# ADUM1250ARZ_v_02.net
KiCad netlist of a schematic drawn in EAGLE
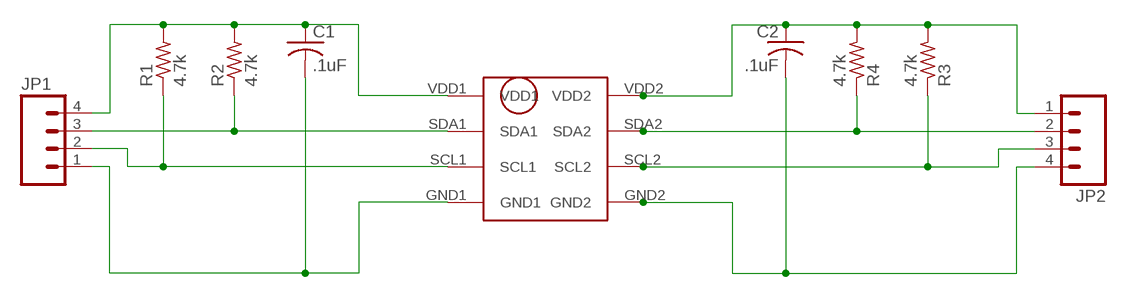
[diagram p0: schematic, sheet 1]

(export (version "E")
  (design (tool "Eeschema 10.0.6"))
  (components
    (comp (ref "C1")
      (value ".1uF")
      (footprint "eagle-import:C0402")
      (libsource (lib "eagle-import") (part "C-USC0402"))
    )
    (comp (ref "C2")
      (value ".1uF")
      (footprint "eagle-import:C0402")
      (libsource (lib "eagle-import") (part "C-USC0402"))
    )
    (comp (ref "JP1")
      (value "M04PTH")
      (footprint "eagle-import:1X04")
      (libsource (lib "eagle-import") (part "M04PTH"))
    )
    (comp (ref "JP2")
      (value "M04PTH")
      (footprint "eagle-import:1X04")
      (libsource (lib "eagle-import") (part "M04PTH"))
    )
    (comp (ref "R1")
      (value "4.7k")
      (footprint "eagle-import:R0402")
      (libsource (lib "eagle-import") (part "R-US_R0402"))
    )
    (comp (ref "R2")
      (value "4.7k")
      (footprint "eagle-import:R0402")
      (libsource (lib "eagle-import") (part "R-US_R0402"))
    )
    (comp (ref "R3")
      (value "4.7k")
      (footprint "eagle-import:R0402")
      (libsource (lib "eagle-import") (part "R-US_R0402"))
    )
    (comp (ref "R4")
      (value "4.7k")
      (footprint "eagle-import:R0402")
      (libsource (lib "eagle-import") (part "R-US_R0402"))
    )
    (comp (ref "U$1")
      (value "ADUM1250ARZ")
      (footprint "eagle-import:ADUM1250ARZ")
      (libsource (lib "eagle-import") (part "ADUM1250ARZ"))
    )
  )
  (nets
    (net (code "1") (name "/GND") (class "Default")
      (node (ref "C1") (pin "2") (pinfunction "2_2") (pintype "passive"))
      (node (ref "C2") (pin "2") (pinfunction "2_2") (pintype "passive"))
      (node (ref "JP1") (pin "1") (pinfunction "1_1") (pintype "passive"))
      (node (ref "JP2") (pin "4") (pinfunction "4_4") (pintype "passive"))
      (node (ref "U$1") (pin "GND1") (pinfunction "GND1_GND1") (pintype "bidirectional"))
      (node (ref "U$1") (pin "GND2") (pinfunction "GND2_GND2") (pintype "bidirectional"))
    )
    (net (code "2") (name "Net-(C1-Pad1)") (class "Default")
      (node (ref "C1") (pin "1") (pinfunction "1_1") (pintype "passive"))
      (node (ref "JP1") (pin "4") (pinfunction "4_4") (pintype "passive"))
      (node (ref "R1") (pin "2") (pinfunction "2_2") (pintype "passive"))
      (node (ref "R2") (pin "2") (pinfunction "2_2") (pintype "passive"))
      (node (ref "U$1") (pin "VDD1") (pinfunction "VDD1_VDD1") (pintype "bidirectional"))
    )
    (net (code "3") (name "Net-(C2-Pad1)") (class "Default")
      (node (ref "C2") (pin "1") (pinfunction "1_1") (pintype "passive"))
      (node (ref "JP2") (pin "1") (pinfunction "1_1") (pintype "passive"))
      (node (ref "R3") (pin "2") (pinfunction "2_2") (pintype "passive"))
      (node (ref "R4") (pin "2") (pinfunction "2_2") (pintype "passive"))
      (node (ref "U$1") (pin "VDD2") (pinfunction "VDD2_VDD2") (pintype "bidirectional"))
    )
    (net (code "4") (name "Net-(JP1-Pad2)") (class "Default")
      (node (ref "JP1") (pin "2") (pinfunction "2_2") (pintype "passive"))
      (node (ref "R1") (pin "1") (pinfunction "1_1") (pintype "passive"))
      (node (ref "U$1") (pin "SCL1") (pinfunction "SCL1_SCL1") (pintype "bidirectional"))
    )
    (net (code "5") (name "Net-(JP1-Pad3)") (class "Default")
      (node (ref "JP1") (pin "3") (pinfunction "3_3") (pintype "passive"))
      (node (ref "R2") (pin "1") (pinfunction "1_1") (pintype "passive"))
      (node (ref "U$1") (pin "SDA1") (pinfunction "SDA1_SDA1") (pintype "bidirectional"))
    )
    (net (code "6") (name "Net-(JP2-Pad2)") (class "Default")
      (node (ref "JP2") (pin "2") (pinfunction "2_2") (pintype "passive"))
      (node (ref "R4") (pin "1") (pinfunction "1_1") (pintype "passive"))
      (node (ref "U$1") (pin "SDA2") (pinfunction "SDA2_SDA2") (pintype "bidirectional"))
    )
    (net (code "7") (name "Net-(JP2-Pad3)") (class "Default")
      (node (ref "JP2") (pin "3") (pinfunction "3_3") (pintype "passive"))
      (node (ref "R3") (pin "1") (pinfunction "1_1") (pintype "passive"))
      (node (ref "U$1") (pin "SCL2") (pinfunction "SCL2_SCL2") (pintype "bidirectional"))
    )
  )
)
